# mosfet.net
KiCad netlist of a schematic drawn in EAGLE
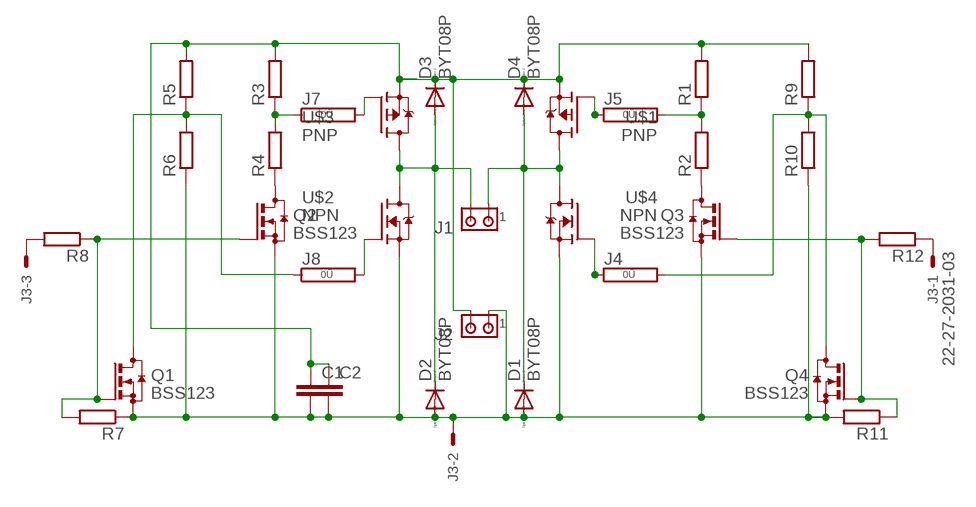
[diagram p0: schematic, sheet 1]

(export (version "E")
  (design (tool "Eeschema 10.0.6"))
  (components
    (comp (ref "C1")
      (value "C-EUC0805")
      (footprint "eagle-import:C0805")
      (libsource (lib "eagle-import") (part "C-EUC0805"))
    )
    (comp (ref "C2")
      (value "C-EUC0805")
      (footprint "eagle-import:C0805")
      (libsource (lib "eagle-import") (part "C-EUC0805"))
    )
    (comp (ref "D1")
      (value "BYT08P")
      (footprint "eagle-import:TO220ACS")
      (libsource (lib "eagle-import") (part "BYT08P"))
    )
    (comp (ref "D2")
      (value "BYT08P")
      (footprint "eagle-import:TO220ACS")
      (libsource (lib "eagle-import") (part "BYT08P"))
    )
    (comp (ref "D3")
      (value "BYT08P")
      (footprint "eagle-import:TO220ACS")
      (libsource (lib "eagle-import") (part "BYT08P"))
    )
    (comp (ref "D4")
      (value "BYT08P")
      (footprint "eagle-import:TO220ACS")
      (libsource (lib "eagle-import") (part "BYT08P"))
    )
    (comp (ref "J1")
      (value "MTA02-156")
      (footprint "eagle-import:1X2MTA")
      (libsource (lib "eagle-import") (part "MTA02-156"))
    )
    (comp (ref "J2")
      (value "MTA02-156")
      (footprint "eagle-import:1X2MTA")
      (libsource (lib "eagle-import") (part "MTA02-156"))
    )
    (comp (ref "J3")
      (value "22-27-2031-03")
      (footprint "eagle-import:6410-03")
      (libsource (lib "eagle-import") (part "22-?-0327-2031"))
    )
    (comp (ref "J4")
      (value "0R")
      (footprint "eagle-import:0R_10")
      (libsource (lib "eagle-import") (part "0R"))
    )
    (comp (ref "J5")
      (value "0R")
      (footprint "eagle-import:0R_10")
      (libsource (lib "eagle-import") (part "0R"))
    )
    (comp (ref "J7")
      (value "0R")
      (footprint "eagle-import:0R_10")
      (libsource (lib "eagle-import") (part "0R"))
    )
    (comp (ref "J8")
      (value "0R")
      (footprint "eagle-import:0R_10")
      (libsource (lib "eagle-import") (part "0R"))
    )
    (comp (ref "Q1")
      (value "BSS123")
      (footprint "eagle-import:SOT23")
      (libsource (lib "eagle-import") (part "BSS123"))
    )
    (comp (ref "Q2")
      (value "BSS123")
      (footprint "eagle-import:SOT23")
      (libsource (lib "eagle-import") (part "BSS123"))
    )
    (comp (ref "Q3")
      (value "BSS123")
      (footprint "eagle-import:SOT23")
      (libsource (lib "eagle-import") (part "BSS123"))
    )
    (comp (ref "Q4")
      (value "BSS123")
      (footprint "eagle-import:SOT23")
      (libsource (lib "eagle-import") (part "BSS123"))
    )
    (comp (ref "R1")
      (value "R-EU_R0805")
      (footprint "eagle-import:R0805")
      (libsource (lib "eagle-import") (part "R-EU_R0805"))
    )
    (comp (ref "R2")
      (value "R-EU_R0805")
      (footprint "eagle-import:R0805")
      (libsource (lib "eagle-import") (part "R-EU_R0805"))
    )
    (comp (ref "R3")
      (value "R-EU_R0805")
      (footprint "eagle-import:R0805")
      (libsource (lib "eagle-import") (part "R-EU_R0805"))
    )
    (comp (ref "R4")
      (value "R-EU_R0805")
      (footprint "eagle-import:R0805")
      (libsource (lib "eagle-import") (part "R-EU_R0805"))
    )
    (comp (ref "R5")
      (value "R-EU_R0805")
      (footprint "eagle-import:R0805")
      (libsource (lib "eagle-import") (part "R-EU_R0805"))
    )
    (comp (ref "R6")
      (value "R-EU_R0805")
      (footprint "eagle-import:R0805")
      (libsource (lib "eagle-import") (part "R-EU_R0805"))
    )
    (comp (ref "R7")
      (value "R-EU_R0805")
      (footprint "eagle-import:R0805")
      (libsource (lib "eagle-import") (part "R-EU_R0805"))
    )
    (comp (ref "R8")
      (value "R-EU_R0805")
      (footprint "eagle-import:R0805")
      (libsource (lib "eagle-import") (part "R-EU_R0805"))
    )
    (comp (ref "R9")
      (value "R-EU_R0805")
      (footprint "eagle-import:R0805")
      (libsource (lib "eagle-import") (part "R-EU_R0805"))
    )
    (comp (ref "R10")
      (value "R-EU_R0805")
      (footprint "eagle-import:R0805")
      (libsource (lib "eagle-import") (part "R-EU_R0805"))
    )
    (comp (ref "R11")
      (value "R-EU_R0805")
      (footprint "eagle-import:R0805")
      (libsource (lib "eagle-import") (part "R-EU_R0805"))
    )
    (comp (ref "R12")
      (value "R-EU_R0805")
      (footprint "eagle-import:R0805")
      (libsource (lib "eagle-import") (part "R-EU_R0805"))
    )
    (comp (ref "U$1")
      (value "PNP")
      (footprint "eagle-import:TO-220")
      (libsource (lib "eagle-import") (part "PNP"))
    )
    (comp (ref "U$2")
      (value "NPN")
      (footprint "eagle-import:TO-247")
      (libsource (lib "eagle-import") (part "NPN"))
    )
    (comp (ref "U$3")
      (value "PNP")
      (footprint "eagle-import:TO-220")
      (libsource (lib "eagle-import") (part "PNP"))
    )
    (comp (ref "U$4")
      (value "NPN")
      (footprint "eagle-import:TO-247")
      (libsource (lib "eagle-import") (part "NPN"))
    )
  )
  (nets
    (net (code "1") (name "Net-(J3A-S)") (class "Default")
      (node (ref "J3") (pin "1") (pinfunction "S_1") (pintype "passive"))
      (node (ref "R12") (pin "1") (pinfunction "1_1") (pintype "passive"))
    )
    (net (code "2") (name "Net-(J3B-S)") (class "Default")
      (node (ref "C1") (pin "2") (pinfunction "2_2") (pintype "passive"))
      (node (ref "C2") (pin "2") (pinfunction "2_2") (pintype "passive"))
      (node (ref "D1") (pin "A") (pinfunction "A_A") (pintype "passive"))
      (node (ref "D2") (pin "A") (pinfunction "A_A") (pintype "passive"))
      (node (ref "J2") (pin "1") (pinfunction "1_1") (pintype "passive"))
      (node (ref "J3") (pin "2") (pinfunction "S_2") (pintype "passive"))
      (node (ref "Q1") (pin "2") (pinfunction "S_2") (pintype "passive"))
      (node (ref "Q2") (pin "2") (pinfunction "S_2") (pintype "passive"))
      (node (ref "Q3") (pin "2") (pinfunction "S_2") (pintype "passive"))
      (node (ref "Q4") (pin "2") (pinfunction "S_2") (pintype "passive"))
      (node (ref "R10") (pin "1") (pinfunction "1_1") (pintype "passive"))
      (node (ref "R11") (pin "2") (pinfunction "2_2") (pintype "passive"))
      (node (ref "R6") (pin "1") (pinfunction "1_1") (pintype "passive"))
      (node (ref "R7") (pin "1") (pinfunction "1_1") (pintype "passive"))
      (node (ref "U$2") (pin "P$3") (pinfunction "S_P$3") (pintype "passive"))
      (node (ref "U$4") (pin "P$3") (pinfunction "S_P$3") (pintype "passive"))
    )
    (net (code "3") (name "Net-(J3C-S)") (class "Default")
      (node (ref "J3") (pin "3") (pinfunction "S_3") (pintype "passive"))
      (node (ref "R8") (pin "2") (pinfunction "2_2") (pintype "passive"))
    )
    (net (code "4") (name "Net-(J5-Pad2)") (class "Default")
      (node (ref "J5") (pin "2") (pinfunction "2_2") (pintype "passive"))
      (node (ref "R1") (pin "1") (pinfunction "1_1") (pintype "passive"))
      (node (ref "R2") (pin "2") (pinfunction "2_2") (pintype "passive"))
    )
    (net (code "5") (name "Net-(J7-Pad1)") (class "Default")
      (node (ref "J7") (pin "1") (pinfunction "1_1") (pintype "passive"))
      (node (ref "R3") (pin "1") (pinfunction "1_1") (pintype "passive"))
      (node (ref "R4") (pin "2") (pinfunction "2_2") (pintype "passive"))
    )
    (net (code "6") (name "Net-(Q1-D)") (class "Default")
      (node (ref "J8") (pin "1") (pinfunction "1_1") (pintype "passive"))
      (node (ref "Q1") (pin "3") (pinfunction "D_3") (pintype "passive"))
      (node (ref "R5") (pin "1") (pinfunction "1_1") (pintype "passive"))
      (node (ref "R6") (pin "2") (pinfunction "2_2") (pintype "passive"))
    )
    (net (code "7") (name "Net-(Q1-G)") (class "Default")
      (node (ref "Q1") (pin "1") (pinfunction "G_1") (pintype "passive"))
      (node (ref "Q2") (pin "1") (pinfunction "G_1") (pintype "passive"))
      (node (ref "R7") (pin "2") (pinfunction "2_2") (pintype "passive"))
      (node (ref "R8") (pin "1") (pinfunction "1_1") (pintype "passive"))
    )
    (net (code "8") (name "Net-(Q2-D)") (class "Default")
      (node (ref "Q2") (pin "3") (pinfunction "D_3") (pintype "passive"))
      (node (ref "R4") (pin "1") (pinfunction "1_1") (pintype "passive"))
    )
    (net (code "9") (name "Net-(Q3-D)") (class "Default")
      (node (ref "Q3") (pin "3") (pinfunction "D_3") (pintype "passive"))
      (node (ref "R2") (pin "1") (pinfunction "1_1") (pintype "passive"))
    )
    (net (code "10") (name "Net-(Q3-G)") (class "Default")
      (node (ref "Q3") (pin "1") (pinfunction "G_1") (pintype "passive"))
      (node (ref "Q4") (pin "1") (pinfunction "G_1") (pintype "passive"))
      (node (ref "R11") (pin "1") (pinfunction "1_1") (pintype "passive"))
      (node (ref "R12") (pin "2") (pinfunction "2_2") (pintype "passive"))
    )
    (net (code "11") (name "Net-(Q4-D)") (class "Default")
      (node (ref "J4") (pin "2") (pinfunction "2_2") (pintype "passive"))
      (node (ref "Q4") (pin "3") (pinfunction "D_3") (pintype "passive"))
      (node (ref "R10") (pin "2") (pinfunction "2_2") (pintype "passive"))
      (node (ref "R9") (pin "1") (pinfunction "1_1") (pintype "passive"))
    )
    (net (code "12") (name "Net-(U$1-D)") (class "Default")
      (node (ref "D1") (pin "C") (pinfunction "C_C") (pintype "passive"))
      (node (ref "D4") (pin "A") (pinfunction "A_A") (pintype "passive"))
      (node (ref "J1") (pin "1") (pinfunction "1_1") (pintype "passive"))
      (node (ref "U$1") (pin "2") (pinfunction "D_2") (pintype "passive"))
      (node (ref "U$4") (pin "P$2") (pinfunction "D_P$2") (pintype "passive"))
    )
    (net (code "13") (name "Net-(U$1-G)") (class "Default")
      (node (ref "J5") (pin "1") (pinfunction "1_1") (pintype "passive"))
      (node (ref "U$1") (pin "1") (pinfunction "G_1") (pintype "passive"))
    )
    (net (code "14") (name "Net-(U$1-S)") (class "Default")
      (node (ref "C1") (pin "1") (pinfunction "1_1") (pintype "passive"))
      (node (ref "C2") (pin "1") (pinfunction "1_1") (pintype "passive"))
      (node (ref "D3") (pin "C") (pinfunction "C_C") (pintype "passive"))
      (node (ref "D4") (pin "C") (pinfunction "C_C") (pintype "passive"))
      (node (ref "J2") (pin "2") (pinfunction "2_2") (pintype "passive"))
      (node (ref "R1") (pin "2") (pinfunction "2_2") (pintype "passive"))
      (node (ref "R3") (pin "2") (pinfunction "2_2") (pintype "passive"))
      (node (ref "R5") (pin "2") (pinfunction "2_2") (pintype "passive"))
      (node (ref "R9") (pin "2") (pinfunction "2_2") (pintype "passive"))
      (node (ref "U$1") (pin "3") (pinfunction "S_3") (pintype "passive"))
      (node (ref "U$3") (pin "3") (pinfunction "S_3") (pintype "passive"))
    )
    (net (code "15") (name "Net-(U$2-D)") (class "Default")
      (node (ref "D2") (pin "C") (pinfunction "C_C") (pintype "passive"))
      (node (ref "D3") (pin "A") (pinfunction "A_A") (pintype "passive"))
      (node (ref "J1") (pin "2") (pinfunction "2_2") (pintype "passive"))
      (node (ref "U$2") (pin "P$2") (pinfunction "D_P$2") (pintype "passive"))
      (node (ref "U$3") (pin "2") (pinfunction "D_2") (pintype "passive"))
    )
    (net (code "16") (name "Net-(U$2-G)") (class "Default")
      (node (ref "J8") (pin "2") (pinfunction "2_2") (pintype "passive"))
      (node (ref "U$2") (pin "P$1") (pinfunction "G_P$1") (pintype "passive"))
    )
    (net (code "17") (name "Net-(U$3-G)") (class "Default")
      (node (ref "J7") (pin "2") (pinfunction "2_2") (pintype "passive"))
      (node (ref "U$3") (pin "1") (pinfunction "G_1") (pintype "passive"))
    )
    (net (code "18") (name "Net-(U$4-G)") (class "Default")
      (node (ref "J4") (pin "1") (pinfunction "1_1") (pintype "passive"))
      (node (ref "U$4") (pin "P$1") (pinfunction "G_P$1") (pintype "passive"))
    )
  )
)
